# SaLAltimeter.net
KiCad netlist of a schematic drawn in EAGLE
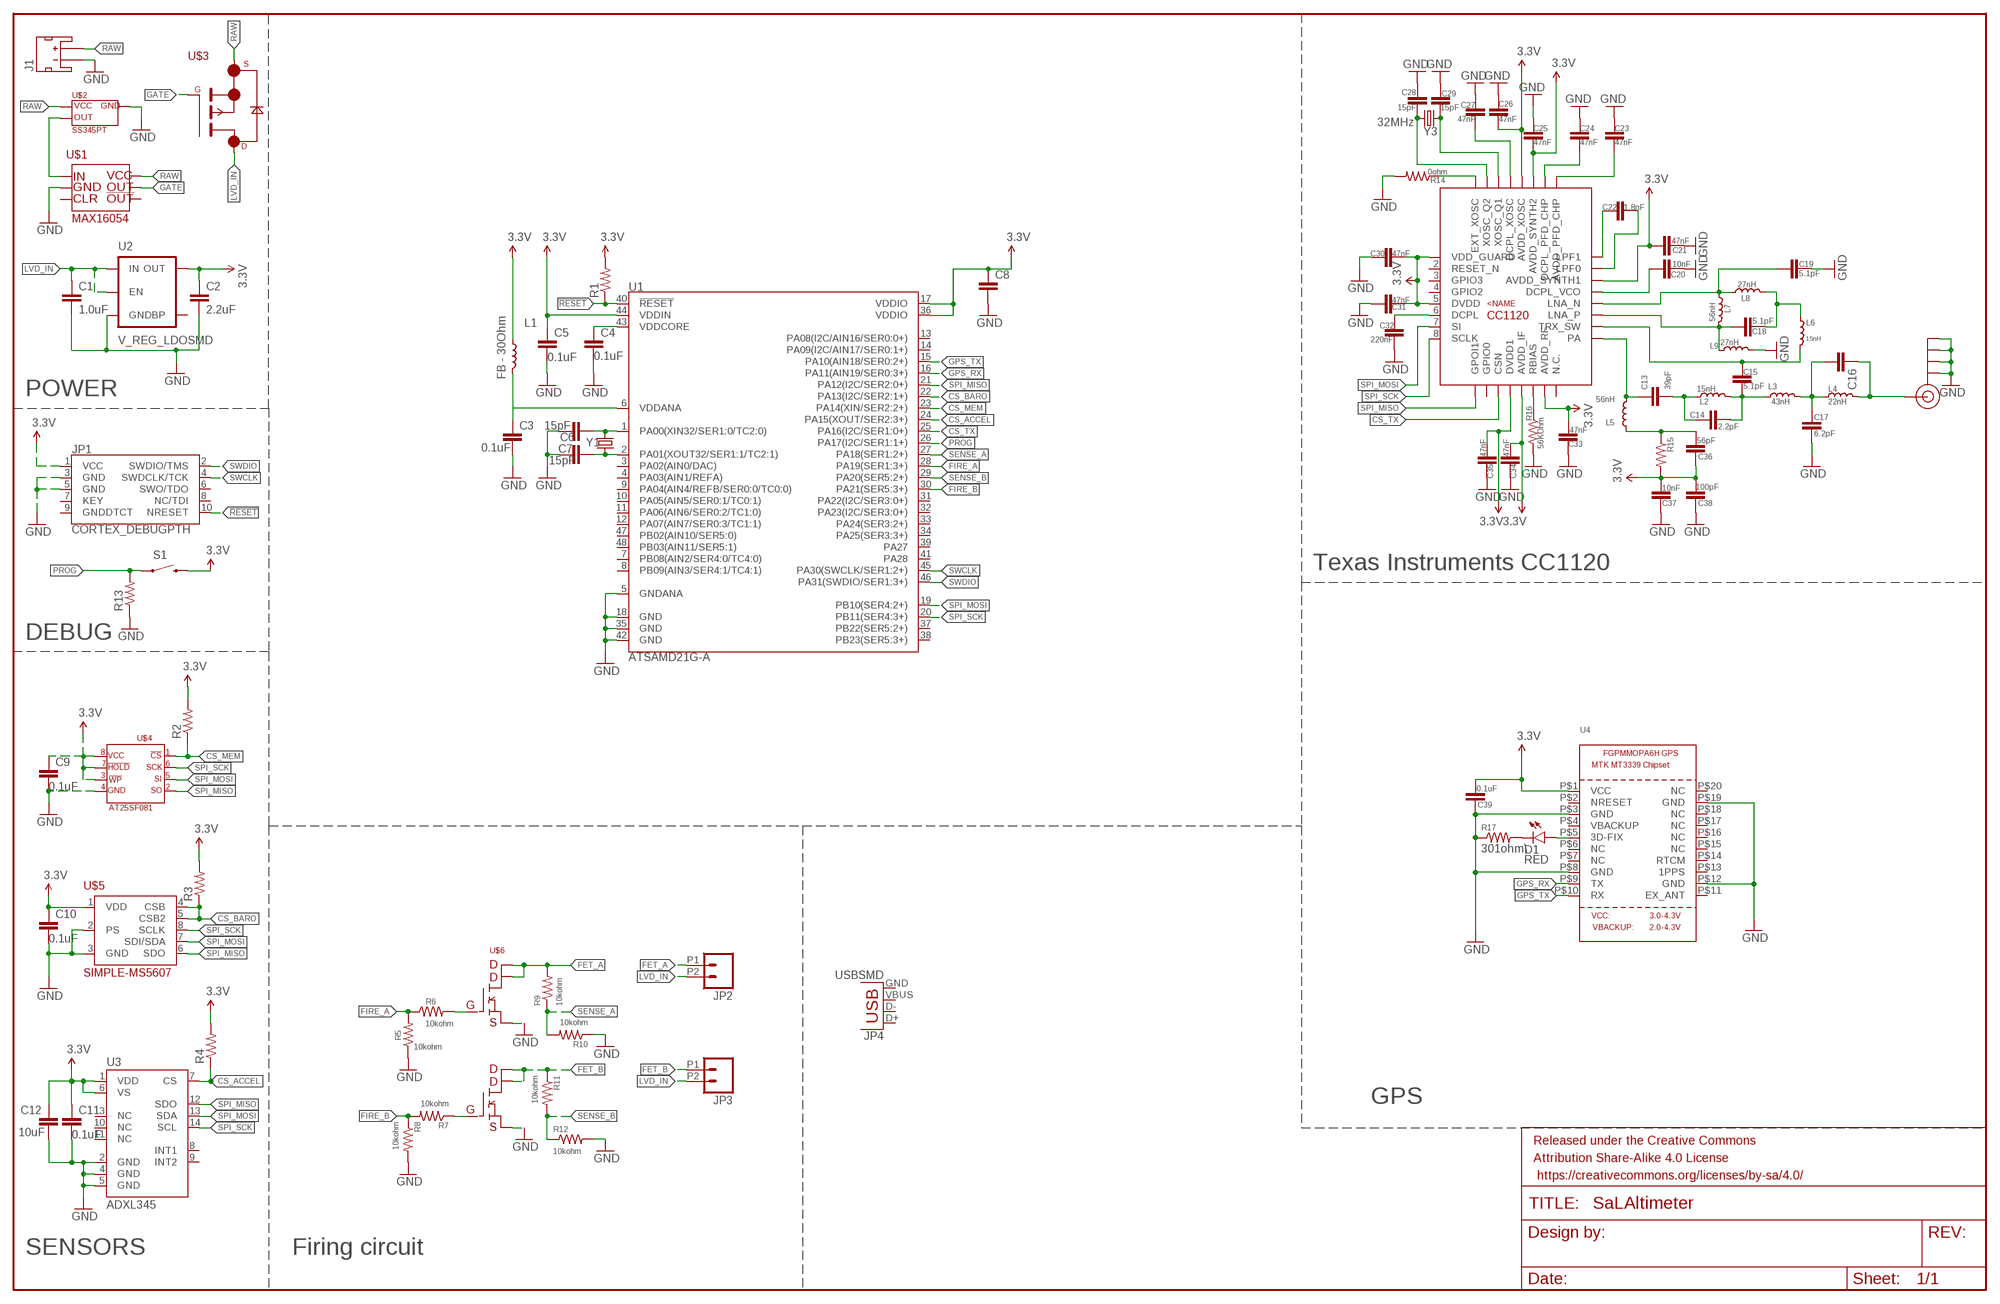
[diagram p0: schematic, sheet 1]

(export (version "E")
  (design (tool "Eeschema 10.0.6"))
  (components
    (comp (ref "C1")
      (value "1.0uF")
      (footprint "eagle-import:0603-CAP")
      (libsource (lib "eagle-import") (part "CAP0603-CAP"))
    )
    (comp (ref "C2")
      (value "2.2uF")
      (footprint "eagle-import:0603-CAP")
      (libsource (lib "eagle-import") (part "CAP0603-CAP"))
    )
    (comp (ref "C3")
      (value "0.1uF")
      (footprint "eagle-import:0402-CAP")
      (libsource (lib "eagle-import") (part "SparkFun-Passives_CAP0402-CAP"))
    )
    (comp (ref "C4")
      (value "0.1uF")
      (footprint "eagle-import:0402-CAP")
      (libsource (lib "eagle-import") (part "SparkFun-Passives_CAP0402-CAP"))
    )
    (comp (ref "C5")
      (value "0.1uF")
      (footprint "eagle-import:0402-CAP")
      (libsource (lib "eagle-import") (part "SparkFun-Passives_CAP0402-CAP"))
    )
    (comp (ref "C6")
      (value "15pF")
      (footprint "eagle-import:0402-CAP")
      (libsource (lib "eagle-import") (part "SparkFun-Passives_CAP0402-CAP"))
    )
    (comp (ref "C7")
      (value "15pF")
      (footprint "eagle-import:0402-CAP")
      (libsource (lib "eagle-import") (part "SparkFun-Passives_CAP0402-CAP"))
    )
    (comp (ref "C8")
      (value "CAP0402-CAP")
      (footprint "eagle-import:0402-CAP")
      (libsource (lib "eagle-import") (part "SparkFun-Passives_CAP0402-CAP"))
    )
    (comp (ref "C9")
      (value "0.1uF")
      (footprint "eagle-import:0402-CAP")
      (libsource (lib "eagle-import") (part "SparkFun-Passives_CAP0402-CAP"))
    )
    (comp (ref "C10")
      (value "0.1uF")
      (footprint "eagle-import:0402-CAP")
      (libsource (lib "eagle-import") (part "SparkFun-Passives_CAP0402-CAP"))
    )
    (comp (ref "C11")
      (value "0.1uF")
      (footprint "eagle-import:0402-CAP")
      (libsource (lib "eagle-import") (part "SparkFun-Passives_CAP0402-CAP"))
    )
    (comp (ref "C12")
      (value "10uF")
      (footprint "eagle-import:0402-CAP")
      (libsource (lib "eagle-import") (part "SparkFun-Passives_CAP0402-CAP"))
    )
    (comp (ref "C13")
      (value "39pF")
      (footprint "eagle-import:0402-CAP")
      (libsource (lib "eagle-import") (part "CAP0402-CAP"))
    )
    (comp (ref "C14")
      (value "2.2pF")
      (footprint "eagle-import:0402-CAP")
      (libsource (lib "eagle-import") (part "CAP0402-CAP"))
    )
    (comp (ref "C15")
      (value "5.1pF")
      (footprint "eagle-import:0402-CAP")
      (libsource (lib "eagle-import") (part "CAP0402-CAP"))
    )
    (comp (ref "C16")
      (value "CAP0402-CAP")
      (footprint "eagle-import:0402-CAP")
      (libsource (lib "eagle-import") (part "CAP0402-CAP"))
    )
    (comp (ref "C17")
      (value "6.2pF")
      (footprint "eagle-import:0402-CAP")
      (libsource (lib "eagle-import") (part "CAP0402-CAP"))
    )
    (comp (ref "C18")
      (value "5.1pF")
      (footprint "eagle-import:0402-CAP")
      (libsource (lib "eagle-import") (part "CAP0402-CAP"))
    )
    (comp (ref "C19")
      (value "5.1pF")
      (footprint "eagle-import:0402-CAP")
      (libsource (lib "eagle-import") (part "CAP0402-CAP"))
    )
    (comp (ref "C20")
      (value "10nF")
      (footprint "eagle-import:0402-CAP")
      (libsource (lib "eagle-import") (part "CAP0402-CAP"))
    )
    (comp (ref "C21")
      (value "47nF")
      (footprint "eagle-import:0402-CAP")
      (libsource (lib "eagle-import") (part "CAP0402-CAP"))
    )
    (comp (ref "C22")
      (value "1.8nF")
      (footprint "eagle-import:0402-CAP")
      (libsource (lib "eagle-import") (part "CAP0402-CAP"))
    )
    (comp (ref "C23")
      (value "47nF")
      (footprint "eagle-import:0402-CAP")
      (libsource (lib "eagle-import") (part "CAP0402-CAP"))
    )
    (comp (ref "C24")
      (value "47nF")
      (footprint "eagle-import:0402-CAP")
      (libsource (lib "eagle-import") (part "CAP0402-CAP"))
    )
    (comp (ref "C25")
      (value "47nF")
      (footprint "eagle-import:0402-CAP")
      (libsource (lib "eagle-import") (part "CAP0402-CAP"))
    )
    (comp (ref "C26")
      (value "47nF")
      (footprint "eagle-import:0402-CAP")
      (libsource (lib "eagle-import") (part "CAP0402-CAP"))
    )
    (comp (ref "C27")
      (value "47nF")
      (footprint "eagle-import:0402-CAP")
      (libsource (lib "eagle-import") (part "CAP0402-CAP"))
    )
    (comp (ref "C28")
      (value "15pF")
      (footprint "eagle-import:0402-CAP")
      (libsource (lib "eagle-import") (part "CAP0402-CAP"))
    )
    (comp (ref "C29")
      (value "15pF")
      (footprint "eagle-import:0402-CAP")
      (libsource (lib "eagle-import") (part "CAP0402-CAP"))
    )
    (comp (ref "C30")
      (value "47nF")
      (footprint "eagle-import:0402-CAP")
      (libsource (lib "eagle-import") (part "CAP0402-CAP"))
    )
    (comp (ref "C31")
      (value "47nF")
      (footprint "eagle-import:0402-CAP")
      (libsource (lib "eagle-import") (part "CAP0402-CAP"))
    )
    (comp (ref "C32")
      (value "220nF")
      (footprint "eagle-import:0402-CAP")
      (libsource (lib "eagle-import") (part "CAP0402-CAP"))
    )
    (comp (ref "C33")
      (value "47nF")
      (footprint "eagle-import:0402-CAP")
      (libsource (lib "eagle-import") (part "CAP0402-CAP"))
    )
    (comp (ref "C34")
      (value "47nF")
      (footprint "eagle-import:0402-CAP")
      (libsource (lib "eagle-import") (part "CAP0402-CAP"))
    )
    (comp (ref "C35")
      (value "47nF")
      (footprint "eagle-import:0402-CAP")
      (libsource (lib "eagle-import") (part "CAP0402-CAP"))
    )
    (comp (ref "C36")
      (value "56pF")
      (footprint "eagle-import:0402-CAP")
      (libsource (lib "eagle-import") (part "CAP0402-CAP"))
    )
    (comp (ref "C37")
      (value "10nF")
      (footprint "eagle-import:0402-CAP")
      (libsource (lib "eagle-import") (part "CAP0402-CAP"))
    )
    (comp (ref "C38")
      (value "100pF")
      (footprint "eagle-import:0402-CAP")
      (libsource (lib "eagle-import") (part "CAP0402-CAP"))
    )
    (comp (ref "C39")
      (value "0.1uF")
      (footprint "eagle-import:0402-CAP")
      (libsource (lib "eagle-import") (part "CAP0402-CAP"))
    )
    (comp (ref "D1")
      (value "RED")
      (footprint "eagle-import:LED-0603")
      (libsource (lib "eagle-import") (part "LED-RED0603"))
    )
    (comp (ref "FRAME1")
      (value "FRAME-LEDGER")
      (footprint "eagle-import:CREATIVE_COMMONS")
      (libsource (lib "eagle-import") (part "FRAME-LEDGER"))
    )
    (comp (ref "J$1")
      (value "SMA_EDGE")
      (footprint "eagle-import:SMA-EDGE")
      (libsource (lib "eagle-import") (part "SMA_EDGE"))
    )
    (comp (ref "J1")
      (value "JST_2MM_MALE")
      (footprint "eagle-import:JST-2-SMD")
      (libsource (lib "eagle-import") (part "JST_2MM_MALE"))
    )
    (comp (ref "JP1")
      (value "CORTEX_DEBUGPTH")
      (footprint "eagle-import:2X5-PTH-1.27MM")
      (libsource (lib "eagle-import") (part "CORTEX_DEBUGPTH"))
    )
    (comp (ref "JP2")
      (value "M022.54MM_SCREWTERM")
      (footprint "eagle-import:1X02_2.54_SCREWTERM")
      (libsource (lib "eagle-import") (part "M022.54MM_SCREWTERM"))
    )
    (comp (ref "JP3")
      (value "M022.54MM_SCREWTERM")
      (footprint "eagle-import:1X02_2.54_SCREWTERM")
      (libsource (lib "eagle-import") (part "M022.54MM_SCREWTERM"))
    )
    (comp (ref "JP4")
      (value "USBSMD")
      (footprint "eagle-import:USB-MINIB")
      (libsource (lib "eagle-import") (part "USBSMD"))
    )
    (comp (ref "L1")
      (value "FB - 30Ohm")
      (footprint "eagle-import:0603")
      (libsource (lib "eagle-import") (part "INDUCTOR0603"))
    )
    (comp (ref "L2")
      (value "15nH")
      (footprint "eagle-import:C0402")
      (libsource (lib "eagle-import") (part "INDUCTOR0402"))
    )
    (comp (ref "L3")
      (value "43nH")
      (footprint "eagle-import:C0402")
      (libsource (lib "eagle-import") (part "INDUCTOR0402"))
    )
    (comp (ref "L4")
      (value "22nH")
      (footprint "eagle-import:C0402")
      (libsource (lib "eagle-import") (part "INDUCTOR0402"))
    )
    (comp (ref "L5")
      (value "56nH")
      (footprint "eagle-import:C0402")
      (libsource (lib "eagle-import") (part "INDUCTOR0402"))
    )
    (comp (ref "L6")
      (value "15nH")
      (footprint "eagle-import:C0402")
      (libsource (lib "eagle-import") (part "INDUCTOR0402"))
    )
    (comp (ref "L7")
      (value "56nH")
      (footprint "eagle-import:C0402")
      (libsource (lib "eagle-import") (part "INDUCTOR0402"))
    )
    (comp (ref "L8")
      (value "27nH")
      (footprint "eagle-import:C0402")
      (libsource (lib "eagle-import") (part "INDUCTOR0402"))
    )
    (comp (ref "L9")
      (value "27nH")
      (footprint "eagle-import:C0402")
      (libsource (lib "eagle-import") (part "INDUCTOR0402"))
    )
    (comp (ref "R1")
      (value "RESISTOR0402-RES")
      (footprint "eagle-import:0402-RES")
      (libsource (lib "eagle-import") (part "RESISTOR0402-RES"))
    )
    (comp (ref "R2")
      (value "RESISTOR0402-RES")
      (footprint "eagle-import:0402-RES")
      (libsource (lib "eagle-import") (part "RESISTOR0402-RES"))
    )
    (comp (ref "R3")
      (value "RESISTOR0402-RES")
      (footprint "eagle-import:0402-RES")
      (libsource (lib "eagle-import") (part "RESISTOR0402-RES"))
    )
    (comp (ref "R4")
      (value "RESISTOR0402-RES")
      (footprint "eagle-import:0402-RES")
      (libsource (lib "eagle-import") (part "RESISTOR0402-RES"))
    )
    (comp (ref "R5")
      (value "10kohm")
      (footprint "eagle-import:0402-RES")
      (libsource (lib "eagle-import") (part "RESISTOR0402"))
    )
    (comp (ref "R6")
      (value "10kohm")
      (footprint "eagle-import:0402-RES")
      (libsource (lib "eagle-import") (part "RESISTOR0402"))
    )
    (comp (ref "R7")
      (value "10kohm")
      (footprint "eagle-import:0402-RES")
      (libsource (lib "eagle-import") (part "RESISTOR0402"))
    )
    (comp (ref "R8")
      (value "10kohm")
      (footprint "eagle-import:0402-RES")
      (libsource (lib "eagle-import") (part "RESISTOR0402"))
    )
    (comp (ref "R9")
      (value "10kohm")
      (footprint "eagle-import:0402-RES")
      (libsource (lib "eagle-import") (part "RESISTOR0402"))
    )
    (comp (ref "R10")
      (value "10kohm")
      (footprint "eagle-import:0402-RES")
      (libsource (lib "eagle-import") (part "RESISTOR0402"))
    )
    (comp (ref "R11")
      (value "10kohm")
      (footprint "eagle-import:0402-RES")
      (libsource (lib "eagle-import") (part "RESISTOR0402"))
    )
    (comp (ref "R12")
      (value "10kohm")
      (footprint "eagle-import:0402-RES")
      (libsource (lib "eagle-import") (part "RESISTOR0402"))
    )
    (comp (ref "R13")
      (value "RESISTOR0402-RES")
      (footprint "eagle-import:0402-RES")
      (libsource (lib "eagle-import") (part "RESISTOR0402-RES"))
    )
    (comp (ref "R14")
      (value "0ohm")
      (footprint "eagle-import:0402-RES")
      (libsource (lib "eagle-import") (part "RESISTOR0402-RES"))
    )
    (comp (ref "R15")
      (value "RESISTOR0402-RES")
      (footprint "eagle-import:0402-RES")
      (libsource (lib "eagle-import") (part "RESISTOR0402-RES"))
    )
    (comp (ref "R16")
      (value "56KOhm")
      (footprint "eagle-import:0402-RES")
      (libsource (lib "eagle-import") (part "RESISTOR0402-RES"))
    )
    (comp (ref "R17")
      (value "301ohm\\")
      (footprint "eagle-import:0402-RES")
      (libsource (lib "eagle-import") (part "RESISTOR0402-RES"))
    )
    (comp (ref "S1")
      (value "SWITCH-MOMENTARY-2SMD-3")
      (footprint "eagle-import:TACTILE_SWITCH_SMD-3")
      (libsource (lib "eagle-import") (part "SWITCH-MOMENTARY-2SMD-3"))
    )
    (comp (ref "U$1")
      (value "MAX16054")
      (footprint "eagle-import:MAX16054")
      (libsource (lib "eagle-import") (part "MAX16054"))
    )
    (comp (ref "U$2")
      (value "SS345PT")
      (footprint "eagle-import:SS345PT")
      (libsource (lib "eagle-import") (part "SS345PT"))
    )
    (comp (ref "U$3")
      (value "SI7615ADN")
      (footprint "eagle-import:SI7615ADN")
      (libsource (lib "eagle-import") (part "SI7615ADN"))
    )
    (comp (ref "U$4")
      (value "AT25SF081")
      (footprint "eagle-import:AT25SF081")
      (libsource (lib "eagle-import") (part "AT25SF081"))
    )
    (comp (ref "U$5")
      (value "SIMPLE-MS5607")
      (footprint "eagle-import:MS5607")
      (libsource (lib "eagle-import") (part "SIMPLE-MS5607"))
    )
    (comp (ref "U$6")
      (value "SI7232DN")
      (footprint "eagle-import:SI7232DN")
      (libsource (lib "eagle-import") (part "SI7232DN"))
    )
    (comp (ref "U$7")
      (value "CC1120")
      (footprint "eagle-import:CC1120")
      (libsource (lib "eagle-import") (part "CC1120"))
    )
    (comp (ref "U1")
      (value "ATSAMD21G-A")
      (footprint "eagle-import:TQFP-48")
      (libsource (lib "eagle-import") (part "ATSAMD21G-A"))
    )
    (comp (ref "U2")
      (value "V_REG_LDOSMD")
      (footprint "eagle-import:SOT23-5")
      (libsource (lib "eagle-import") (part "V_REG_LDOSMD"))
    )
    (comp (ref "U3")
      (value "ADXL345")
      (footprint "eagle-import:LGA14")
      (libsource (lib "eagle-import") (part "ADXL345"))
    )
    (comp (ref "U4")
      (value "GPS_FGPMMOPA6H")
      (footprint "eagle-import:FGPMMOPA6H")
      (libsource (lib "eagle-import") (part "GPS_FGPMMOPA6H"))
    )
    (comp (ref "Y1")
      (value "CRYSTAL3.2X1.5MM")
      (footprint "eagle-import:CRYSTAL-SMD-3.2X1.5MM")
      (libsource (lib "eagle-import") (part "CRYSTAL3.2X1.5MM"))
    )
    (comp (ref "Y3")
      (value "32MHz")
      (footprint "eagle-import:CRYSTAL-SMD-5X3")
      (libsource (lib "eagle-import") (part "CRYSTAL5X3"))
    )
  )
  (nets
    (net (code "1") (name "/~{RESET}") (class "Default")
      (node (ref "JP1") (pin "10") (pinfunction "NRESET_10") (pintype "bidirectional"))
      (node (ref "R1") (pin "1") (pinfunction "1_1") (pintype "passive"))
      (node (ref "U1") (pin "40") (pinfunction "~{RESET}_40") (pintype "bidirectional"))
    )
    (net (code "2") (name "3.3V") (class "Default")
      (node (ref "C10") (pin "1") (pinfunction "1_1") (pintype "passive"))
      (node (ref "C11") (pin "1") (pinfunction "1_1") (pintype "passive"))
      (node (ref "C12") (pin "1") (pinfunction "1_1") (pintype "passive"))
      (node (ref "C2") (pin "1") (pinfunction "1_1") (pintype "passive"))
      (node (ref "C21") (pin "1") (pinfunction "1_1") (pintype "passive"))
      (node (ref "C25") (pin "2") (pinfunction "2_2") (pintype "passive"))
      (node (ref "C26") (pin "2") (pinfunction "2_2") (pintype "passive"))
      (node (ref "C30") (pin "2") (pinfunction "2_2") (pintype "passive"))
      (node (ref "C31") (pin "2") (pinfunction "2_2") (pintype "passive"))
      (node (ref "C33") (pin "2") (pinfunction "2_2") (pintype "passive"))
      (node (ref "C34") (pin "2") (pinfunction "2_2") (pintype "passive"))
      (node (ref "C35") (pin "2") (pinfunction "2_2") (pintype "passive"))
      (node (ref "C36") (pin "1") (pinfunction "1_1") (pintype "passive"))
      (node (ref "C37") (pin "2") (pinfunction "2_2") (pintype "passive"))
      (node (ref "C38") (pin "2") (pinfunction "2_2") (pintype "passive"))
      (node (ref "C39") (pin "2") (pinfunction "2_2") (pintype "passive"))
      (node (ref "C5") (pin "1") (pinfunction "1_1") (pintype "passive"))
      (node (ref "C8") (pin "1") (pinfunction "1_1") (pintype "passive"))
      (node (ref "C9") (pin "1") (pinfunction "1_1") (pintype "passive"))
      (node (ref "JP1") (pin "1") (pinfunction "VCC_1") (pintype "bidirectional"))
      (node (ref "L1") (pin "1") (pinfunction "1_1") (pintype "passive"))
      (node (ref "R1") (pin "2") (pinfunction "2_2") (pintype "passive"))
      (node (ref "R15") (pin "2") (pinfunction "2_2") (pintype "passive"))
      (node (ref "R2") (pin "2") (pinfunction "2_2") (pintype "passive"))
      (node (ref "R3") (pin "2") (pinfunction "2_2") (pintype "passive"))
      (node (ref "R4") (pin "2") (pinfunction "2_2") (pintype "passive"))
      (node (ref "S1") (pin "4") (pinfunction "2_4") (pintype "passive"))
      (node (ref "U$4") (pin "!HOLD") (pinfunction "~{HOLD}_!HOLD") (pintype "bidirectional"))
      (node (ref "U$4") (pin "!WP") (pinfunction "~{WP}_!WP") (pintype "bidirectional"))
      (node (ref "U$4") (pin "VCC") (pinfunction "VCC_VCC") (pintype "bidirectional"))
      (node (ref "U$5") (pin "1") (pinfunction "VDD_1") (pintype "bidirectional"))
      (node (ref "U$7") (pin "1") (pinfunction "VDD_GUARD_1") (pintype "bidirectional"))
      (node (ref "U$7") (pin "12") (pinfunction "DVDD1_12") (pintype "bidirectional"))
      (node (ref "U$7") (pin "13") (pinfunction "AVDD_IF_13") (pintype "bidirectional"))
      (node (ref "U$7") (pin "15") (pinfunction "AVDD_RF_15") (pintype "bidirectional"))
      (node (ref "U$7") (pin "22") (pinfunction "AVDD_SYNTH1_22") (pintype "bidirectional"))
      (node (ref "U$7") (pin "27") (pinfunction "AVDD_SYNTH2_27") (pintype "bidirectional"))
      (node (ref "U$7") (pin "28") (pinfunction "AVDD_XOSC_28") (pintype "bidirectional"))
      (node (ref "U$7") (pin "5") (pinfunction "DVDD_5") (pintype "bidirectional"))
      (node (ref "U1") (pin "17") (pinfunction "VDDIO_17") (pintype "bidirectional"))
      (node (ref "U1") (pin "36") (pinfunction "VDDIO_36") (pintype "bidirectional"))
      (node (ref "U1") (pin "44") (pinfunction "VDDIN_44") (pintype "bidirectional"))
      (node (ref "U2") (pin "5") (pinfunction "OUT_5") (pintype "passive"))
      (node (ref "U3") (pin "1") (pinfunction "VDD_1") (pintype "bidirectional"))
      (node (ref "U3") (pin "6") (pinfunction "VS_6") (pintype "bidirectional"))
      (node (ref "U4") (pin "P$1") (pinfunction "VCC_P$1") (pintype "bidirectional"))
    )
    (net (code "3") (name "CS_ACCEL") (class "Default")
      (node (ref "R4") (pin "1") (pinfunction "1_1") (pintype "passive"))
      (node (ref "U1") (pin "24") (pinfunction "PA15(XOUT/SER2:3+)_24") (pintype "bidirectional"))
      (node (ref "U3") (pin "7") (pinfunction "CS_7") (pintype "bidirectional"))
    )
    (net (code "4") (name "CS_BARO") (class "Default")
      (node (ref "R3") (pin "1") (pinfunction "1_1") (pintype "passive"))
      (node (ref "U$5") (pin "4") (pinfunction "CSB_4") (pintype "bidirectional"))
      (node (ref "U$5") (pin "5") (pinfunction "CSB2_5") (pintype "bidirectional"))
      (node (ref "U1") (pin "22") (pinfunction "PA13(I2C/SER2:1+)_22") (pintype "bidirectional"))
    )
    (net (code "5") (name "CS_MEM") (class "Default")
      (node (ref "R2") (pin "1") (pinfunction "1_1") (pintype "passive"))
      (node (ref "U$4") (pin "!CS") (pinfunction "~{CS}_!CS") (pintype "bidirectional"))
      (node (ref "U1") (pin "23") (pinfunction "PA14(XIN/SER2:2+)_23") (pintype "bidirectional"))
    )
    (net (code "6") (name "CS_TX") (class "Default")
      (node (ref "U$7") (pin "11") (pinfunction "CSN_11") (pintype "bidirectional"))
      (node (ref "U1") (pin "25") (pinfunction "PA16(I2C/SER1:0+)_25") (pintype "bidirectional"))
    )
    (net (code "7") (name "FET_A") (class "Default")
      (node (ref "JP2") (pin "P1") (pinfunction "1_P1") (pintype "passive"))
      (node (ref "R9") (pin "2") (pinfunction "2_2") (pintype "passive"))
      (node (ref "U$6") (pin "7") (pinfunction "PIN7_7") (pintype "bidirectional"))
      (node (ref "U$6") (pin "8") (pinfunction "PIN8_8") (pintype "bidirectional"))
    )
    (net (code "8") (name "FET_B") (class "Default")
      (node (ref "JP3") (pin "P1") (pinfunction "1_P1") (pintype "passive"))
      (node (ref "R11") (pin "1") (pinfunction "1_1") (pintype "passive"))
      (node (ref "U$6") (pin "5") (pinfunction "PIN5_5") (pintype "bidirectional"))
      (node (ref "U$6") (pin "6") (pinfunction "PIN6_6") (pintype "bidirectional"))
    )
    (net (code "9") (name "FIRE_A") (class "Default")
      (node (ref "R5") (pin "2") (pinfunction "2_2") (pintype "passive"))
      (node (ref "R6") (pin "1") (pinfunction "1_1") (pintype "passive"))
      (node (ref "U1") (pin "28") (pinfunction "PA19(SER1:3+)_28") (pintype "bidirectional"))
    )
    (net (code "10") (name "FIRE_B") (class "Default")
      (node (ref "R7") (pin "2") (pinfunction "2_2") (pintype "passive"))
      (node (ref "R8") (pin "1") (pinfunction "1_1") (pintype "passive"))
      (node (ref "U1") (pin "30") (pinfunction "PA21(SER5:3+)_30") (pintype "bidirectional"))
    )
    (net (code "11") (name "GATE") (class "Default")
      (node (ref "U$1") (pin "OUT") (pinfunction "OUT_OUT") (pintype "bidirectional"))
      (node (ref "U$3") (pin "G") (pinfunction "G_G") (pintype "bidirectional"))
    )
    (net (code "12") (name "GND") (class "Default")
      (node (ref "C1") (pin "2") (pinfunction "2_2") (pintype "passive"))
      (node (ref "C10") (pin "2") (pinfunction "2_2") (pintype "passive"))
      (node (ref "C11") (pin "2") (pinfunction "2_2") (pintype "passive"))
      (node (ref "C12") (pin "2") (pinfunction "2_2") (pintype "passive"))
      (node (ref "C17") (pin "2") (pinfunction "2_2") (pintype "passive"))
      (node (ref "C19") (pin "2") (pinfunction "2_2") (pintype "passive"))
      (node (ref "C2") (pin "2") (pinfunction "2_2") (pintype "passive"))
      (node (ref "C20") (pin "2") (pinfunction "2_2") (pintype "passive"))
      (node (ref "C21") (pin "2") (pinfunction "2_2") (pintype "passive"))
      (node (ref "C23") (pin "1") (pinfunction "1_1") (pintype "passive"))
      (node (ref "C24") (pin "1") (pinfunction "1_1") (pintype "passive"))
      (node (ref "C25") (pin "1") (pinfunction "1_1") (pintype "passive"))
      (node (ref "C26") (pin "1") (pinfunction "1_1") (pintype "passive"))
      (node (ref "C27") (pin "1") (pinfunction "1_1") (pintype "passive"))
      (node (ref "C28") (pin "1") (pinfunction "1_1") (pintype "passive"))
      (node (ref "C29") (pin "1") (pinfunction "1_1") (pintype "passive"))
      (node (ref "C3") (pin "2") (pinfunction "2_2") (pintype "passive"))
      (node (ref "C30") (pin "1") (pinfunction "1_1") (pintype "passive"))
      (node (ref "C31") (pin "1") (pinfunction "1_1") (pintype "passive"))
      (node (ref "C32") (pin "1") (pinfunction "1_1") (pintype "passive"))
      (node (ref "C33") (pin "1") (pinfunction "1_1") (pintype "passive"))
      (node (ref "C34") (pin "1") (pinfunction "1_1") (pintype "passive"))
      (node (ref "C35") (pin "1") (pinfunction "1_1") (pintype "passive"))
      (node (ref "C37") (pin "1") (pinfunction "1_1") (pintype "passive"))
      (node (ref "C38") (pin "1") (pinfunction "1_1") (pintype "passive"))
      (node (ref "C39") (pin "1") (pinfunction "1_1") (pintype "passive"))
      (node (ref "C4") (pin "2") (pinfunction "2_2") (pintype "passive"))
      (node (ref "C5") (pin "2") (pinfunction "2_2") (pintype "passive"))
      (node (ref "C6") (pin "2") (pinfunction "2_2") (pintype "passive"))
      (node (ref "C7") (pin "2") (pinfunction "2_2") (pintype "passive"))
      (node (ref "C8") (pin "2") (pinfunction "2_2") (pintype "passive"))
      (node (ref "C9") (pin "2") (pinfunction "2_2") (pintype "passive"))
      (node (ref "J$1") (pin "GND@0") (pinfunction "GND_GND@0") (pintype "bidirectional"))
      (node (ref "J$1") (pin "GND@1") (pinfunction "GND_GND@1") (pintype "bidirectional"))
      (node (ref "J$1") (pin "GND@2") (pinfunction "GND_GND@2") (pintype "bidirectional"))
      (node (ref "J$1") (pin "GND@3") (pinfunction "GND_GND@3") (pintype "bidirectional"))
      (node (ref "J1") (pin "1") (pinfunction "-_1") (pintype "bidirectional"))
      (node (ref "JP1") (pin "3") (pinfunction "GND_3") (pintype "bidirectional"))
      (node (ref "JP1") (pin "5") (pinfunction "GND_5") (pintype "bidirectional"))
      (node (ref "L9") (pin "2") (pinfunction "2_2") (pintype "passive"))
      (node (ref "R10") (pin "1") (pinfunction "1_1") (pintype "passive"))
      (node (ref "R12") (pin "2") (pinfunction "2_2") (pintype "passive"))
      (node (ref "R13") (pin "1") (pinfunction "1_1") (pintype "passive"))
      (node (ref "R14") (pin "2") (pinfunction "2_2") (pintype "passive"))
      (node (ref "R16") (pin "2") (pinfunction "2_2") (pintype "passive"))
      (node (ref "R17") (pin "1") (pinfunction "1_1") (pintype "passive"))
      (node (ref "R5") (pin "1") (pinfunction "1_1") (pintype "passive"))
      (node (ref "R8") (pin "2") (pinfunction "2_2") (pintype "passive"))
      (node (ref "U$1") (pin "GND") (pinfunction "GND_GND") (pintype "bidirectional"))
      (node (ref "U$2") (pin "GND") (pinfunction "GND_GND") (pintype "bidirectional"))
      (node (ref "U$4") (pin "GND") (pinfunction "GND_GND") (pintype "bidirectional"))
      (node (ref "U$5") (pin "2") (pinfunction "PS_2") (pintype "bidirectional"))
      (node (ref "U$5") (pin "3") (pinfunction "GND_3") (pintype "bidirectional"))
      (node (ref "U$6") (pin "1") (pinfunction "PIN1_1") (pintype "bidirectional"))
      (node (ref "U$6") (pin "3") (pinfunction "PIN3_3") (pintype "bidirectional"))
      (node (ref "U1") (pin "18") (pinfunction "GND_18") (pintype "bidirectional"))
      (node (ref "U1") (pin "35") (pinfunction "GND_35") (pintype "bidirectional"))
      (node (ref "U1") (pin "42") (pinfunction "GND_42") (pintype "bidirectional"))
      (node (ref "U1") (pin "5") (pinfunction "GNDANA_5") (pintype "bidirectional"))
      (node (ref "U2") (pin "2") (pinfunction "GND_2") (pintype "input"))
      (node (ref "U3") (pin "2") (pinfunction "GND_2") (pintype "bidirectional"))
      (node (ref "U3") (pin "4") (pinfunction "GND_4") (pintype "bidirectional"))
      (node (ref "U3") (pin "5") (pinfunction "GND_5") (pintype "bidirectional"))
      (node (ref "U4") (pin "P$12") (pinfunction "GND_P$12") (pintype "bidirectional"))
      (node (ref "U4") (pin "P$19") (pinfunction "GND_P$19") (pintype "bidirectional"))
      (node (ref "U4") (pin "P$3") (pinfunction "GND_P$3") (pintype "bidirectional"))
      (node (ref "U4") (pin "P$8") (pinfunction "GND_P$8") (pintype "bidirectional"))
    )
    (net (code "13") (name "GPS_RX") (class "Default")
      (node (ref "U1") (pin "16") (pinfunction "PA11(AIN19/SER0:3+)_16") (pintype "bidirectional"))
      (node (ref "U4") (pin "P$9") (pinfunction "TX_P$9") (pintype "bidirectional"))
    )
    (net (code "14") (name "GPS_TX") (class "Default")
      (node (ref "U1") (pin "15") (pinfunction "PA10(AIN18/SER0:2+)_15") (pintype "bidirectional"))
      (node (ref "U4") (pin "P$10") (pinfunction "RX_P$10") (pintype "bidirectional"))
    )
    (net (code "15") (name "LVD_IN") (class "Default")
      (node (ref "C1") (pin "1") (pinfunction "1_1") (pintype "passive"))
      (node (ref "JP2") (pin "P2") (pinfunction "2_P2") (pintype "passive"))
      (node (ref "JP3") (pin "P2") (pinfunction "2_P2") (pintype "passive"))
      (node (ref "U$3") (pin "D1") (pinfunction "D_D1") (pintype "bidirectional"))
      (node (ref "U$3") (pin "D2") (pinfunction "D_D2") (pintype "bidirectional"))
      (node (ref "U$3") (pin "D3") (pinfunction "D_D3") (pintype "bidirectional"))
      (node (ref "U$3") (pin "D4") (pinfunction "D_D4") (pintype "bidirectional"))
      (node (ref "U2") (pin "1") (pinfunction "IN_1") (pintype "input"))
      (node (ref "U2") (pin "3") (pinfunction "EN_3") (pintype "input"))
    )
    (net (code "16") (name "Net-(C3-Pad1)") (class "Default")
      (node (ref "C3") (pin "1") (pinfunction "1_1") (pintype "passive"))
      (node (ref "L1") (pin "2") (pinfunction "2_2") (pintype "passive"))
    )
    (net (code "17") (name "Net-(C13-Pad2)") (class "Default")
      (node (ref "C13") (pin "2") (pinfunction "2_2") (pintype "passive"))
      (node (ref "C14") (pin "1") (pinfunction "1_1") (pintype "passive"))
      (node (ref "L2") (pin "1") (pinfunction "1_1") (pintype "passive"))
    )
    (net (code "18") (name "Net-(C14-Pad2)") (class "Default")
      (node (ref "C14") (pin "2") (pinfunction "2_2") (pintype "passive"))
      (node (ref "C15") (pin "1") (pinfunction "1_1") (pintype "passive"))
      (node (ref "L2") (pin "2") (pinfunction "2_2") (pintype "passive"))
      (node (ref "L3") (pin "1") (pinfunction "1_1") (pintype "passive"))
    )
    (net (code "19") (name "Net-(C16-Pad2)") (class "Default")
      (node (ref "C16") (pin "2") (pinfunction "2_2") (pintype "passive"))
      (node (ref "C17") (pin "1") (pinfunction "1_1") (pintype "passive"))
      (node (ref "L3") (pin "2") (pinfunction "2_2") (pintype "passive"))
      (node (ref "L4") (pin "1") (pinfunction "1_1") (pintype "passive"))
    )
    (net (code "20") (name "Net-(C18-Pad2)") (class "Default")
      (node (ref "C18") (pin "2") (pinfunction "2_2") (pintype "passive"))
      (node (ref "L6") (pin "1") (pinfunction "1_1") (pintype "passive"))
      (node (ref "L8") (pin "2") (pinfunction "2_2") (pintype "passive"))
    )
    (net (code "21") (name "Net-(C36-Pad2)") (class "Default")
      (node (ref "C36") (pin "2") (pinfunction "2_2") (pintype "passive"))
      (node (ref "L5") (pin "1") (pinfunction "1_1") (pintype "passive"))
      (node (ref "R15") (pin "1") (pinfunction "1_1") (pintype "passive"))
    )
    (net (code "22") (name "Net-(D1-PadC)") (class "Default")
      (node (ref "D1") (pin "C") (pinfunction "C_C") (pintype "passive"))
      (node (ref "R17") (pin "2") (pinfunction "2_2") (pintype "passive"))
    )
    (net (code "23") (name "Net-(J$1-SIGNAL)") (class "Default")
      (node (ref "C16") (pin "1") (pinfunction "1_1") (pintype "passive"))
      (node (ref "J$1") (pin "SIG") (pinfunction "SIGNAL_SIG") (pintype "bidirectional"))
      (node (ref "L4") (pin "2") (pinfunction "2_2") (pintype "passive"))
    )
    (net (code "24") (name "Net-(U$1-PadIN)") (class "Default")
      (node (ref "U$1") (pin "IN") (pinfunction "IN_IN") (pintype "bidirectional"))
      (node (ref "U$2") (pin "OUT") (pinfunction "OUT_OUT") (pintype "bidirectional"))
    )
    (net (code "25") (name "Net-(U$6-PIN2)") (class "Default")
      (node (ref "R6") (pin "2") (pinfunction "2_2") (pintype "passive"))
      (node (ref "U$6") (pin "2") (pinfunction "PIN2_2") (pintype "bidirectional"))
    )
    (net (code "26") (name "Net-(U$6-PIN4)") (class "Default")
      (node (ref "R7") (pin "1") (pinfunction "1_1") (pintype "passive"))
      (node (ref "U$6") (pin "4") (pinfunction "PIN4_4") (pintype "bidirectional"))
    )
    (net (code "27") (name "Net-(U$7-AVDD_PFD_CHP)") (class "Default")
      (node (ref "C23") (pin "2") (pinfunction "2_2") (pintype "passive"))
      (node (ref "U$7") (pin "25") (pinfunction "AVDD_PFD_CHP_25") (pintype "bidirectional"))
    )
    (net (code "28") (name "Net-(U$7-DCPL)") (class "Default")
      (node (ref "C32") (pin "2") (pinfunction "2_2") (pintype "passive"))
      (node (ref "U$7") (pin "6") (pinfunction "DCPL_6") (pintype "bidirectional"))
    )
    (net (code "29") (name "Net-(U$7-DCPL_PFD_CHP)") (class "Default")
      (node (ref "C24") (pin "2") (pinfunction "2_2") (pintype "passive"))
      (node (ref "U$7") (pin "26") (pinfunction "DCPL_PFD_CHP_26") (pintype "bidirectional"))
    )
    (net (code "30") (name "Net-(U$7-DCPL_VCO)") (class "Default")
      (node (ref "C20") (pin "1") (pinfunction "1_1") (pintype "passive"))
      (node (ref "U$7") (pin "21") (pinfunction "DCPL_VCO_21") (pintype "bidirectional"))
    )
    (net (code "31") (name "Net-(U$7-DCPL_XOSC)") (class "Default")
      (node (ref "C27") (pin "2") (pinfunction "2_2") (pintype "passive"))
      (node (ref "U$7") (pin "29") (pinfunction "DCPL_XOSC_29") (pintype "bidirectional"))
    )
    (net (code "32") (name "Net-(U$7-EXT_XOSC)") (class "Default")
      (node (ref "R14") (pin "1") (pinfunction "1_1") (pintype "passive"))
      (node (ref "U$7") (pin "32") (pinfunction "EXT_XOSC_32") (pintype "bidirectional"))
    )
    (net (code "33") (name "Net-(U$7-LNA_N)") (class "Default")
      (node (ref "C19") (pin "1") (pinfunction "1_1") (pintype "passive"))
      (node (ref "L7") (pin "1") (pinfunction "1_1") (pintype "passive"))
      (node (ref "L8") (pin "1") (pinfunction "1_1") (pintype "passive"))
      (node (ref "U$7") (pin "20") (pinfunction "LNA_N_20") (pintype "bidirectional"))
    )
    (net (code "34") (name "Net-(U$7-LNA_P)") (class "Default")
      (node (ref "C18") (pin "1") (pinfunction "1_1") (pintype "passive"))
      (node (ref "L7") (pin "2") (pinfunction "2_2") (pintype "passive"))
      (node (ref "L9") (pin "1") (pinfunction "1_1") (pintype "passive"))
      (node (ref "U$7") (pin "19") (pinfunction "LNA_P_19") (pintype "bidirectional"))
    )
    (net (code "35") (name "Net-(U$7-LPF0)") (class "Default")
      (node (ref "C22") (pin "2") (pinfunction "2_2") (pintype "passive"))
      (node (ref "U$7") (pin "23") (pinfunction "LPF0_23") (pintype "bidirectional"))
    )
    (net (code "36") (name "Net-(U$7-LPF1)") (class "Default")
      (node (ref "C22") (pin "1") (pinfunction "1_1") (pintype "passive"))
      (node (ref "U$7") (pin "24") (pinfunction "LPF1_24") (pintype "bidirectional"))
    )
    (net (code "37") (name "Net-(U$7-PA)") (class "Default")
      (node (ref "C13") (pin "1") (pinfunction "1_1") (pintype "passive"))
      (node (ref "L5") (pin "2") (pinfunction "2_2") (pintype "passive"))
      (node (ref "U$7") (pin "17") (pinfunction "PA_17") (pintype "bidirectional"))
    )
    (net (code "38") (name "Net-(U$7-RBIAS)") (class "Default")
      (node (ref "R16") (pin "1") (pinfunction "1_1") (pintype "passive"))
      (node (ref "U$7") (pin "14") (pinfunction "RBIAS_14") (pintype "bidirectional"))
    )
    (net (code "39") (name "Net-(U$7-TRX_SW)") (class "Default")
      (node (ref "C15") (pin "2") (pinfunction "2_2") (pintype "passive"))
      (node (ref "L6") (pin "2") (pinfunction "2_2") (pintype "passive"))
      (node (ref "U$7") (pin "18") (pinfunction "TRX_SW_18") (pintype "bidirectional"))
    )
    (net (code "40") (name "Net-(U$7-XOSC_Q1)") (class "Default")
      (node (ref "C29") (pin "2") (pinfunction "2_2") (pintype "passive"))
      (node (ref "U$7") (pin "30") (pinfunction "XOSC_Q1_30") (pintype "bidirectional"))
      (node (ref "Y3") (pin "3") (pinfunction "2_3") (pintype "passive"))
    )
    (net (code "41") (name "Net-(U$7-XOSC_Q2)") (class "Default")
      (node (ref "C28") (pin "2") (pinfunction "2_2") (pintype "passive"))
      (node (ref "U$7") (pin "31") (pinfunction "XOSC_Q2_31") (pintype "bidirectional"))
      (node (ref "Y3") (pin "1") (pinfunction "1_1") (pintype "passive"))
    )
    (net (code "42") (name "Net-(U1-PA00(XIN32{slash}SER1:0{slash}TC2:0))") (class "Default")
      (node (ref "C6") (pin "1") (pinfunction "1_1") (pintype "passive"))
      (node (ref "U1") (pin "1") (pinfunction "PA00(XIN32/SER1:0/TC2:0)_1") (pintype "bidirectional"))
      (node (ref "Y1") (pin "P$2") (pinfunction "2_P$2") (pintype "passive"))
    )
    (net (code "43") (name "Net-(U1-PA01(XOUT32{slash}SER1:1{slash}TC2:1))") (class "Default")
      (node (ref "C7") (pin "1") (pinfunction "1_1") (pintype "passive"))
      (node (ref "U1") (pin "2") (pinfunction "PA01(XOUT32/SER1:1/TC2:1)_2") (pintype "bidirectional"))
      (node (ref "Y1") (pin "P$1") (pinfunction "1_P$1") (pintype "passive"))
    )
    (net (code "44") (name "Net-(U1-VDDCORE)") (class "Default")
      (node (ref "C4") (pin "1") (pinfunction "1_1") (pintype "passive"))
      (node (ref "U1") (pin "43") (pinfunction "VDDCORE_43") (pintype "bidirectional"))
    )
    (net (code "45") (name "Net-(U4-3D-FIX)") (class "Default")
      (node (ref "D1") (pin "A") (pinfunction "A_A") (pintype "passive"))
      (node (ref "U4") (pin "P$5") (pinfunction "3D-FIX_P$5") (pintype "bidirectional"))
    )
    (net (code "46") (name "PROG") (class "Default")
      (node (ref "R13") (pin "2") (pinfunction "2_2") (pintype "passive"))
      (node (ref "S1") (pin "1") (pinfunction "1_1") (pintype "passive"))
      (node (ref "U1") (pin "26") (pinfunction "PA17(I2C/SER1:1+)_26") (pintype "bidirectional"))
    )
    (net (code "47") (name "RAW") (class "Default")
      (node (ref "J1") (pin "2") (pinfunction "+_2") (pintype "bidirectional"))
      (node (ref "U$1") (pin "VCC") (pinfunction "VCC_VCC") (pintype "bidirectional"))
      (node (ref "U$2") (pin "VCC") (pinfunction "VCC_VCC") (pintype "bidirectional"))
      (node (ref "U$3") (pin "S1") (pinfunction "S_S1") (pintype "bidirectional"))
      (node (ref "U$3") (pin "S2") (pinfunction "S_S2") (pintype "bidirectional"))
      (node (ref "U$3") (pin "S3") (pinfunction "S_S3") (pintype "bidirectional"))
    )
    (net (code "48") (name "SENSE_A") (class "Default")
      (node (ref "R10") (pin "2") (pinfunction "2_2") (pintype "passive"))
      (node (ref "R9") (pin "1") (pinfunction "1_1") (pintype "passive"))
      (node (ref "U1") (pin "27") (pinfunction "PA18(SER1:2+)_27") (pintype "bidirectional"))
    )
    (net (code "49") (name "SENSE_B") (class "Default")
      (node (ref "R11") (pin "2") (pinfunction "2_2") (pintype "passive"))
      (node (ref "R12") (pin "1") (pinfunction "1_1") (pintype "passive"))
      (node (ref "U1") (pin "29") (pinfunction "PA20(SER5:2+)_29") (pintype "bidirectional"))
    )
    (net (code "50") (name "SPI_MISO") (class "Default")
      (node (ref "U$4") (pin "SO") (pinfunction "SO_SO") (pintype "bidirectional"))
      (node (ref "U$5") (pin "6") (pinfunction "SDO_6") (pintype "bidirectional"))
      (node (ref "U$7") (pin "9") (pinfunction "GPOI1_9") (pintype "bidirectional"))
      (node (ref "U1") (pin "21") (pinfunction "PA12(I2C/SER2:0+)_21") (pintype "bidirectional"))
      (node (ref "U3") (pin "12") (pinfunction "SDO_12") (pintype "bidirectional"))
    )
    (net (code "51") (name "SPI_MOSI") (class "Default")
      (node (ref "U$4") (pin "SI") (pinfunction "SI_SI") (pintype "bidirectional"))
      (node (ref "U$5") (pin "7") (pinfunction "SDI/SDA_7") (pintype "bidirectional"))
      (node (ref "U$7") (pin "7") (pinfunction "SI_7") (pintype "bidirectional"))
      (node (ref "U1") (pin "19") (pinfunction "PB10(SER4:2+)_19") (pintype "bidirectional"))
      (node (ref "U3") (pin "13") (pinfunction "SDA_13") (pintype "bidirectional"))
    )
    (net (code "52") (name "SPI_SCK") (class "Default")
      (node (ref "U$4") (pin "SCK") (pinfunction "SCK_SCK") (pintype "bidirectional"))
      (node (ref "U$5") (pin "8") (pinfunction "SCLK_8") (pintype "bidirectional"))
      (node (ref "U$7") (pin "8") (pinfunction "SCLK_8") (pintype "bidirectional"))
      (node (ref "U1") (pin "20") (pinfunction "PB11(SER4:3+)_20") (pintype "bidirectional"))
      (node (ref "U3") (pin "14") (pinfunction "SCL_14") (pintype "bidirectional"))
    )
    (net (code "53") (name "SWCLK") (class "Default")
      (node (ref "JP1") (pin "4") (pinfunction "SWDCLK/TCK_4") (pintype "bidirectional"))
      (node (ref "U1") (pin "45") (pinfunction "PA30(SWCLK/SER1:2+)_45") (pintype "bidirectional"))
    )
    (net (code "54") (name "SWDIO") (class "Default")
      (node (ref "JP1") (pin "2") (pinfunction "SWDIO/TMS_2") (pintype "bidirectional"))
      (node (ref "U1") (pin "46") (pinfunction "PA31(SWDIO/SER1:3+)_46") (pintype "bidirectional"))
    )
    (net (code "55") (name "unconnected-(J1-PAD1-PadNC1)") (class "Default")
      (node (ref "J1") (pin "NC1") (pinfunction "PAD1_NC1") (pintype "bidirectional"))
    )
    (net (code "56") (name "unconnected-(J1-PAD2-PadNC2)") (class "Default")
      (node (ref "J1") (pin "NC2") (pinfunction "PAD2_NC2") (pintype "bidirectional"))
    )
    (net (code "57") (name "unconnected-(JP1-GNDDTCT-Pad9)") (class "Default")
      (node (ref "JP1") (pin "9") (pinfunction "GNDDTCT_9") (pintype "bidirectional"))
    )
    (net (code "58") (name "unconnected-(JP1-KEY-Pad7)") (class "Default")
      (node (ref "JP1") (pin "7") (pinfunction "KEY_7") (pintype "bidirectional"))
    )
    (net (code "59") (name "unconnected-(JP1-NC{slash}TDI-Pad8)") (class "Default")
      (node (ref "JP1") (pin "8") (pinfunction "NC/TDI_8") (pintype "bidirectional"))
    )
    (net (code "60") (name "unconnected-(JP1-SWO{slash}TDO-Pad6)") (class "Default")
      (node (ref "JP1") (pin "6") (pinfunction "SWO/TDO_6") (pintype "bidirectional"))
    )
    (net (code "61") (name "unconnected-(JP4-PadD+)") (class "Default")
      (node (ref "JP4") (pin "D+") (pinfunction "D+_D+") (pintype "bidirectional"))
    )
    (net (code "62") (name "unconnected-(JP4-PadD-)") (class "Default")
      (node (ref "JP4") (pin "D-") (pinfunction "D-_D-") (pintype "bidirectional"))
    )
    (net (code "63") (name "unconnected-(JP4-PadGND)") (class "Default")
      (node (ref "JP4") (pin "GND") (pinfunction "GND_GND") (pintype "bidirectional"))
    )
    (net (code "64") (name "unconnected-(JP4-PadVBUS)") (class "Default")
      (node (ref "JP4") (pin "VBUS") (pinfunction "VBUS_VBUS") (pintype "bidirectional"))
    )
    (net (code "65") (name "unconnected-(U$1-PadCLR)") (class "Default")
      (node (ref "U$1") (pin "CLR") (pinfunction "CLR_CLR") (pintype "bidirectional"))
    )
    (net (code "66") (name "unconnected-(U$1-~{OUT}-Pad!OUT)") (class "Default")
      (node (ref "U$1") (pin "!OUT") (pinfunction "~{OUT}_!OUT") (pintype "bidirectional"))
    )
    (net (code "67") (name "unconnected-(U$7-GPIO0-Pad10)") (class "Default")
      (node (ref "U$7") (pin "10") (pinfunction "GPIO0_10") (pintype "bidirectional"))
    )
    (net (code "68") (name "unconnected-(U$7-GPIO2-Pad4)") (class "Default")
      (node (ref "U$7") (pin "4") (pinfunction "GPIO2_4") (pintype "bidirectional"))
    )
    (net (code "69") (name "unconnected-(U$7-GPIO3-Pad3)") (class "Default")
      (node (ref "U$7") (pin "3") (pinfunction "GPIO3_3") (pintype "bidirectional"))
    )
    (net (code "70") (name "unconnected-(U$7-N.C.-Pad16)") (class "Default")
      (node (ref "U$7") (pin "16") (pinfunction "N.C._16") (pintype "bidirectional"))
    )
    (net (code "71") (name "unconnected-(U$7-RESET_N-Pad2)") (class "Default")
      (node (ref "U$7") (pin "2") (pinfunction "RESET_N_2") (pintype "bidirectional"))
    )
    (net (code "72") (name "unconnected-(U1-PA02(AIN0{slash}DAC)-Pad3)") (class "Default")
      (node (ref "U1") (pin "3") (pinfunction "PA02(AIN0/DAC)_3") (pintype "bidirectional"))
    )
    (net (code "73") (name "unconnected-(U1-PA03(AIN1{slash}REFA)-Pad4)") (class "Default")
      (node (ref "U1") (pin "4") (pinfunction "PA03(AIN1/REFA)_4") (pintype "bidirectional"))
    )
    (net (code "74") (name "unconnected-(U1-PA04(AIN4{slash}REFB{slash}SER0:0{slash}TC0:0)-Pad9)") (class "Default")
      (node (ref "U1") (pin "9") (pinfunction "PA04(AIN4/REFB/SER0:0/TC0:0)_9") (pintype "bidirectional"))
    )
    (net (code "75") (name "unconnected-(U1-PA05(AIN5{slash}SER0:1{slash}TC0:1)-Pad10)") (class "Default")
      (node (ref "U1") (pin "10") (pinfunction "PA05(AIN5/SER0:1/TC0:1)_10") (pintype "bidirectional"))
    )
    (net (code "76") (name "unconnected-(U1-PA06(AIN6{slash}SER0:2{slash}TC1:0)-Pad11)") (class "Default")
      (node (ref "U1") (pin "11") (pinfunction "PA06(AIN6/SER0:2/TC1:0)_11") (pintype "bidirectional"))
    )
    (net (code "77") (name "unconnected-(U1-PA07(AIN7{slash}SER0:3{slash}TC1:1)-Pad12)") (class "Default")
      (node (ref "U1") (pin "12") (pinfunction "PA07(AIN7/SER0:3/TC1:1)_12") (pintype "bidirectional"))
    )
    (net (code "78") (name "unconnected-(U1-PA08(I2C{slash}AIN16{slash}SER0:0+)-Pad13)") (class "Default")
      (node (ref "U1") (pin "13") (pinfunction "PA08(I2C/AIN16/SER0:0+)_13") (pintype "bidirectional"))
    )
    (net (code "79") (name "unconnected-(U1-PA09(I2C{slash}AIN17{slash}SER0:1+)-Pad14)") (class "Default")
      (node (ref "U1") (pin "14") (pinfunction "PA09(I2C/AIN17/SER0:1+)_14") (pintype "bidirectional"))
    )
    (net (code "80") (name "unconnected-(U1-PA22(I2C{slash}SER3:0+)-Pad31)") (class "Default")
      (node (ref "U1") (pin "31") (pinfunction "PA22(I2C/SER3:0+)_31") (pintype "bidirectional"))
    )
    (net (code "81") (name "unconnected-(U1-PA23(I2C{slash}SER3:0+)-Pad32)") (class "Default")
      (node (ref "U1") (pin "32") (pinfunction "PA23(I2C/SER3:0+)_32") (pintype "bidirectional"))
    )
    (net (code "82") (name "unconnected-(U1-PA24(SER3:2+)-Pad33)") (class "Default")
      (node (ref "U1") (pin "33") (pinfunction "PA24(SER3:2+)_33") (pintype "bidirectional"))
    )
    (net (code "83") (name "unconnected-(U1-PA25(SER3:3+)-Pad34)") (class "Default")
      (node (ref "U1") (pin "34") (pinfunction "PA25(SER3:3+)_34") (pintype "bidirectional"))
    )
    (net (code "84") (name "unconnected-(U1-PA27-Pad39)") (class "Default")
      (node (ref "U1") (pin "39") (pinfunction "PA27_39") (pintype "bidirectional"))
    )
    (net (code "85") (name "unconnected-(U1-PA28-Pad41)") (class "Default")
      (node (ref "U1") (pin "41") (pinfunction "PA28_41") (pintype "bidirectional"))
    )
    (net (code "86") (name "unconnected-(U1-PB02(AIN10{slash}SER5:0)-Pad47)") (class "Default")
      (node (ref "U1") (pin "47") (pinfunction "PB02(AIN10/SER5:0)_47") (pintype "bidirectional"))
    )
    (net (code "87") (name "unconnected-(U1-PB03(AIN11{slash}SER5:1)-Pad48)") (class "Default")
      (node (ref "U1") (pin "48") (pinfunction "PB03(AIN11/SER5:1)_48") (pintype "bidirectional"))
    )
    (net (code "88") (name "unconnected-(U1-PB08(AIN2{slash}SER4:0{slash}TC4:0)-Pad7)") (class "Default")
      (node (ref "U1") (pin "7") (pinfunction "PB08(AIN2/SER4:0/TC4:0)_7") (pintype "bidirectional"))
    )
    (net (code "89") (name "unconnected-(U1-PB09(AIN3{slash}SER4:1{slash}TC4:1)-Pad8)") (class "Default")
      (node (ref "U1") (pin "8") (pinfunction "PB09(AIN3/SER4:1/TC4:1)_8") (pintype "bidirectional"))
    )
    (net (code "90") (name "unconnected-(U1-PB22(SER5:2+)-Pad37)") (class "Default")
      (node (ref "U1") (pin "37") (pinfunction "PB22(SER5:2+)_37") (pintype "bidirectional"))
    )
    (net (code "91") (name "unconnected-(U1-PB23(SER5:3+)-Pad38)") (class "Default")
      (node (ref "U1") (pin "38") (pinfunction "PB23(SER5:3+)_38") (pintype "bidirectional"))
    )
    (net (code "92") (name "unconnected-(U1-VDDANA-Pad6)") (class "Default")
      (node (ref "U1") (pin "6") (pinfunction "VDDANA_6") (pintype "bidirectional"))
    )
    (net (code "93") (name "unconnected-(U2-BP-Pad4)") (class "Default")
      (node (ref "U2") (pin "4") (pinfunction "BP_4") (pintype "input"))
    )
    (net (code "94") (name "unconnected-(U3-INT1-Pad8)") (class "Default")
      (node (ref "U3") (pin "8") (pinfunction "INT1_8") (pintype "bidirectional"))
    )
    (net (code "95") (name "unconnected-(U3-INT2-Pad9)") (class "Default")
      (node (ref "U3") (pin "9") (pinfunction "INT2_9") (pintype "bidirectional"))
    )
    (net (code "96") (name "unconnected-(U3-NC-Pad3)") (class "Default")
      (node (ref "U3") (pin "3") (pinfunction "NC_3") (pintype "bidirectional"))
    )
    (net (code "97") (name "unconnected-(U3-NC-Pad10)") (class "Default")
      (node (ref "U3") (pin "10") (pinfunction "NC_10") (pintype "bidirectional"))
    )
    (net (code "98") (name "unconnected-(U3-NC-Pad11)") (class "Default")
      (node (ref "U3") (pin "11") (pinfunction "NC_11") (pintype "bidirectional"))
    )
    (net (code "99") (name "unconnected-(U4-1PPS-PadP$13)") (class "Default")
      (node (ref "U4") (pin "P$13") (pinfunction "1PPS_P$13") (pintype "bidirectional"))
    )
    (net (code "100") (name "unconnected-(U4-EX_ANT-PadP$11)") (class "Default")
      (node (ref "U4") (pin "P$11") (pinfunction "EX_ANT_P$11") (pintype "bidirectional"))
    )
    (net (code "101") (name "unconnected-(U4-NC-PadP$6)") (class "Default")
      (node (ref "U4") (pin "P$6") (pinfunction "NC_P$6") (pintype "bidirectional"))
    )
    (net (code "102") (name "unconnected-(U4-NC-PadP$7)") (class "Default")
      (node (ref "U4") (pin "P$7") (pinfunction "NC_P$7") (pintype "bidirectional"))
    )
    (net (code "103") (name "unconnected-(U4-NC-PadP$15)") (class "Default")
      (node (ref "U4") (pin "P$15") (pinfunction "NC_P$15") (pintype "bidirectional"))
    )
    (net (code "104") (name "unconnected-(U4-NC-PadP$16)") (class "Default")
      (node (ref "U4") (pin "P$16") (pinfunction "NC_P$16") (pintype "bidirectional"))
    )
    (net (code "105") (name "unconnected-(U4-NC-PadP$17)") (class "Default")
      (node (ref "U4") (pin "P$17") (pinfunction "NC_P$17") (pintype "bidirectional"))
    )
    (net (code "106") (name "unconnected-(U4-NC-PadP$18)") (class "Default")
      (node (ref "U4") (pin "P$18") (pinfunction "NC_P$18") (pintype "bidirectional"))
    )
    (net (code "107") (name "unconnected-(U4-NC-PadP$20)") (class "Default")
      (node (ref "U4") (pin "P$20") (pinfunction "NC_P$20") (pintype "bidirectional"))
    )
    (net (code "108") (name "unconnected-(U4-NRESET-PadP$2)") (class "Default")
      (node (ref "U4") (pin "P$2") (pinfunction "NRESET_P$2") (pintype "bidirectional"))
    )
    (net (code "109") (name "unconnected-(U4-RTCM-PadP$14)") (class "Default")
      (node (ref "U4") (pin "P$14") (pinfunction "RTCM_P$14") (pintype "bidirectional"))
    )
    (net (code "110") (name "unconnected-(U4-VBACKUP-PadP$4)") (class "Default")
      (node (ref "U4") (pin "P$4") (pinfunction "VBACKUP_P$4") (pintype "bidirectional"))
    )
  )
)
